# Channels.net
KiCad netlist of a schematic drawn in Altium Designer
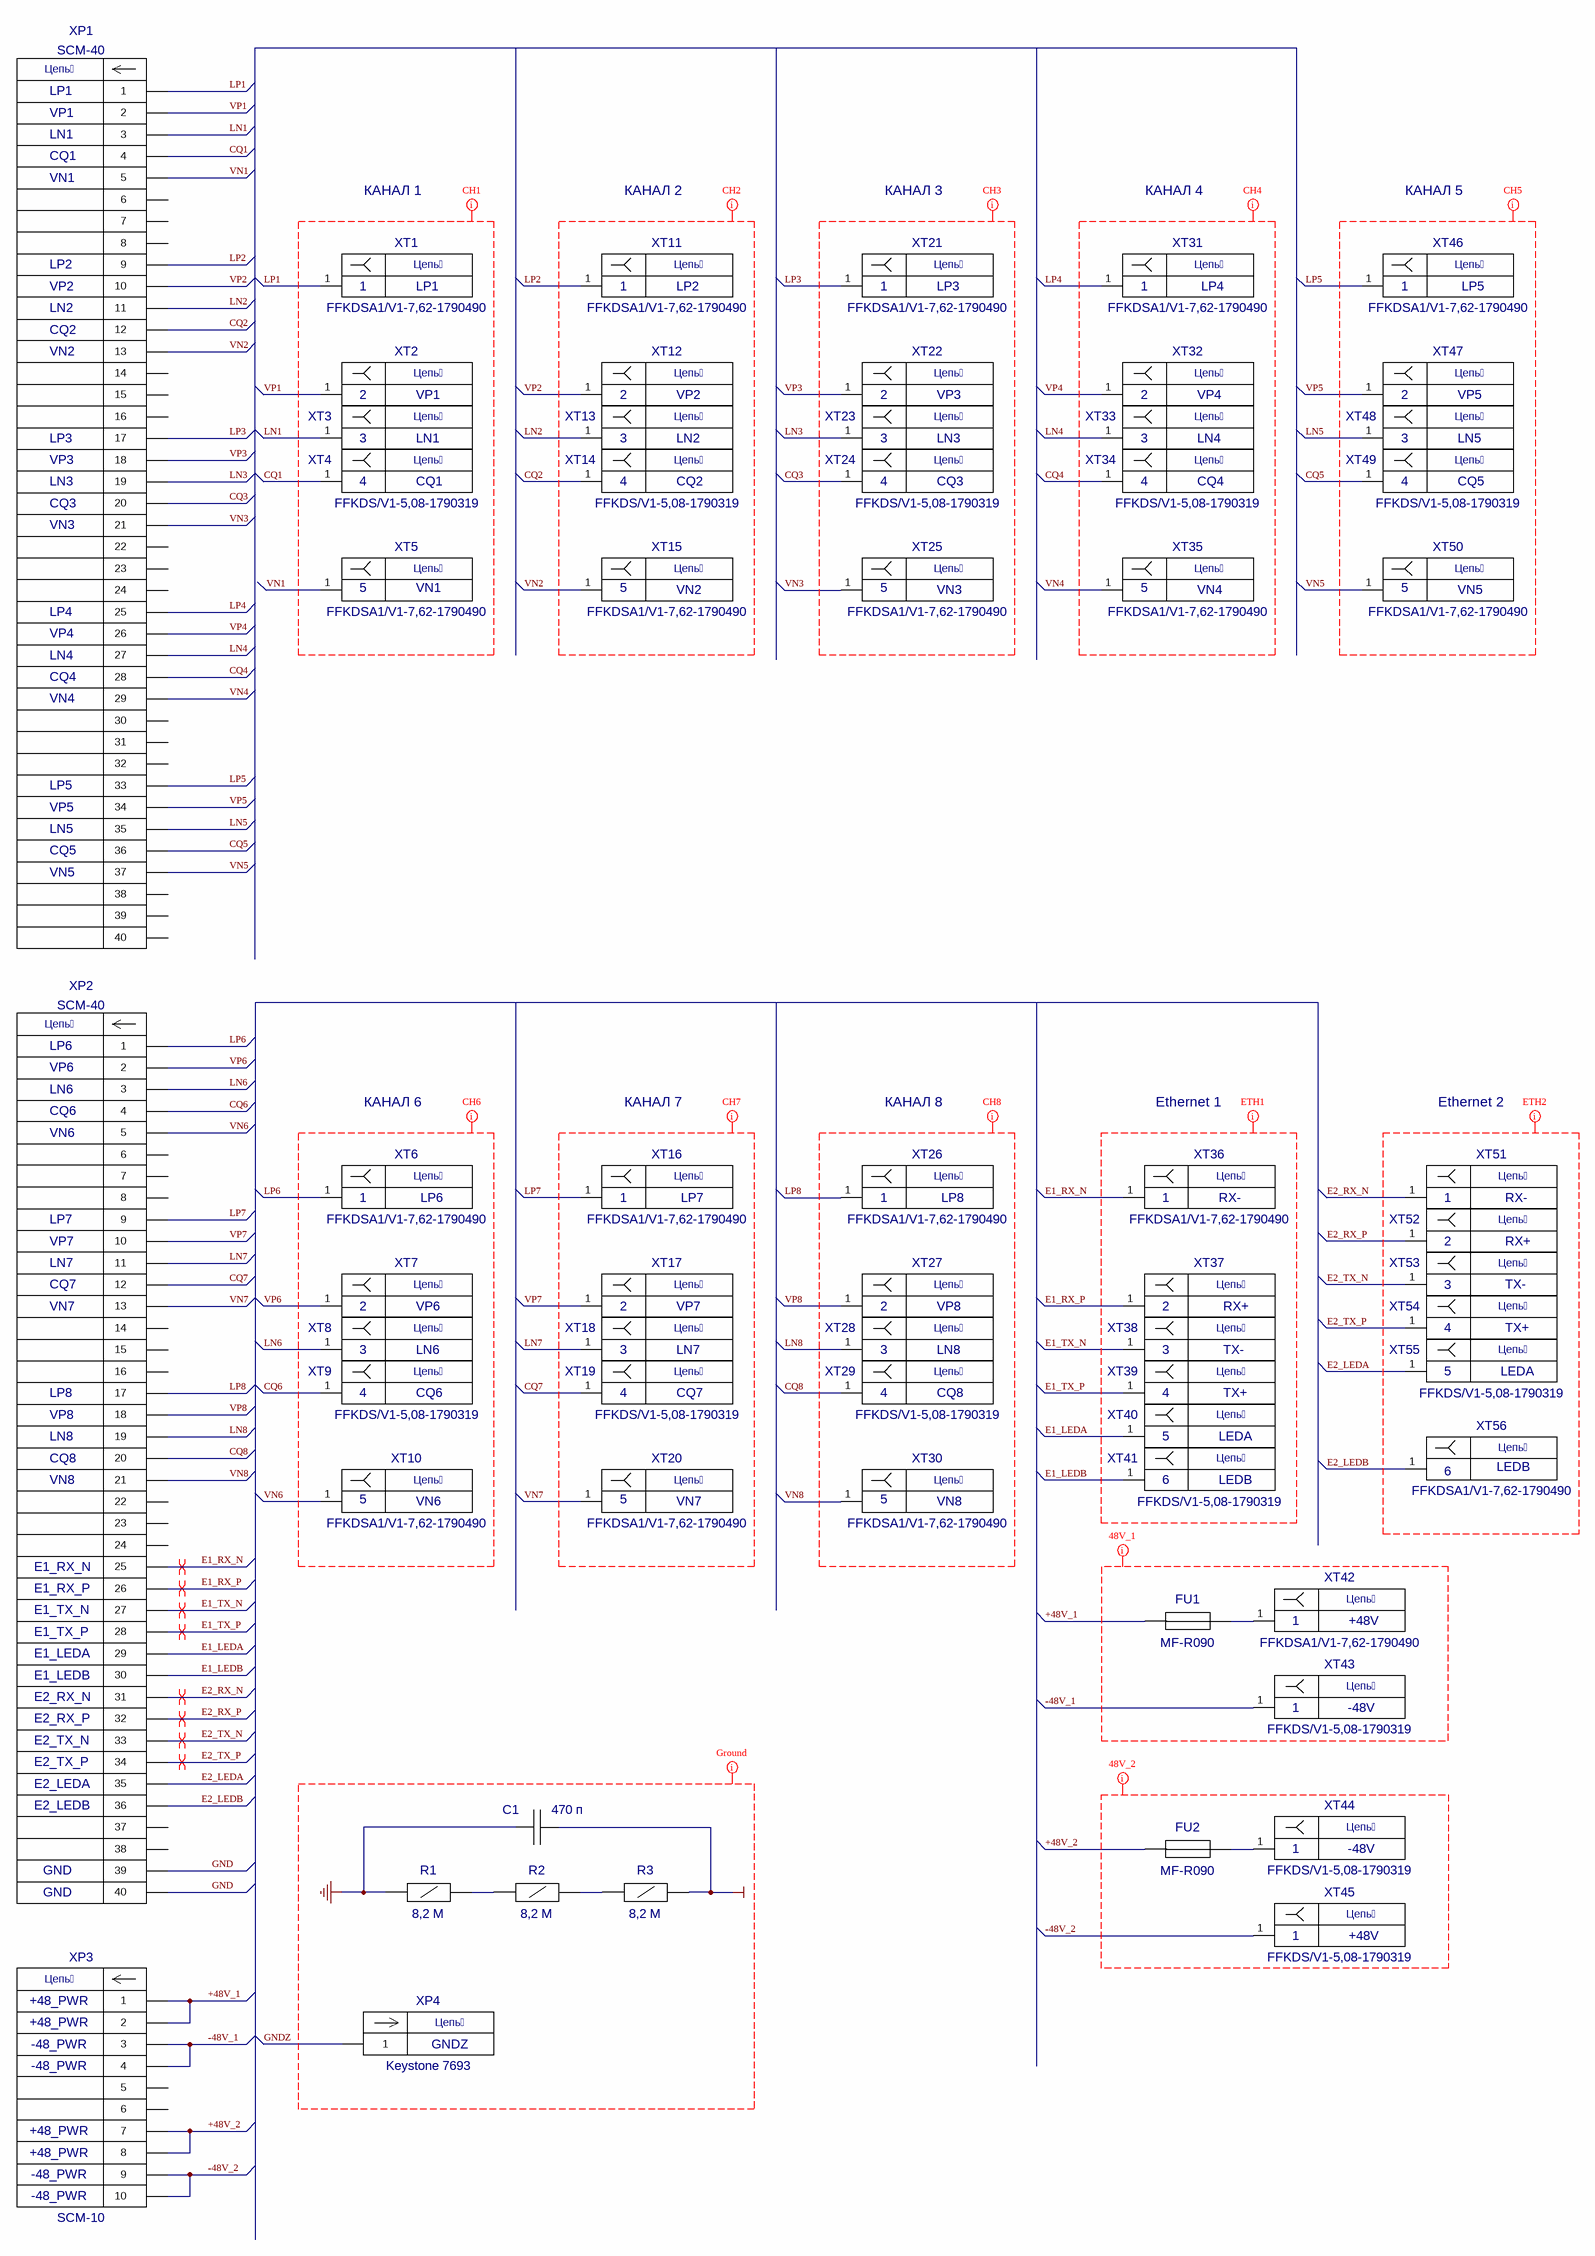
[diagram p0: Channels.SchDoc]

(export (version "E")
  (design (tool "Eeschema 10.0.6"))
  (components
    (comp (ref "C1")
      (value "470 п")
      (footprint "1812")
      (fields
        (field (name "TOLERANCE") "± 10 %")
        (field (name "VOLTAGE") "3 кВ")
        (field (name "Comment") "C1812")
      )
      (libsource (lib "Capacitor-IPC7351-N") (part "C1812"))
    )
    (comp (ref "FU1")
      (value "MF-R090")
      (footprint "MF-R090")
      (libsource (lib "Fuse-IPC7351-N") (part "MF-R090"))
    )
    (comp (ref "FU2")
      (value "MF-R090")
      (footprint "MF-R090")
      (libsource (lib "Fuse-IPC7351-N") (part "MF-R090"))
    )
    (comp (ref "R1")
      (value "8,2 М")
      (footprint "1206")
      (fields
        (field (name "POWER") "0,25 Вт")
        (field (name "TOLERANCE") "± 5 %")
        (field (name "Comment") "R1206")
      )
      (libsource (lib "Resistor-IPC7351-N") (part "R1206"))
    )
    (comp (ref "R2")
      (value "8,2 М")
      (footprint "1206")
      (fields
        (field (name "POWER") "0,25 Вт")
        (field (name "TOLERANCE") "± 5 %")
        (field (name "Comment") "R1206")
      )
      (libsource (lib "Resistor-IPC7351-N") (part "R1206"))
    )
    (comp (ref "R3")
      (value "8,2 М")
      (footprint "1206")
      (fields
        (field (name "POWER") "0,25 Вт")
        (field (name "TOLERANCE") "± 5 %")
        (field (name "Comment") "R1206")
      )
      (libsource (lib "Resistor-IPC7351-N") (part "R1206"))
    )
    (comp (ref "XP1")
      (value "SCM-40")
      (footprint "SCM-40")
      (libsource (lib "Connect-IPC7351-N") (part "SCM-40"))
    )
    (comp (ref "XP2")
      (value "SCM-40")
      (footprint "SCM-40")
      (libsource (lib "Connect-IPC7351-N") (part "SCM-40"))
    )
    (comp (ref "XP3")
      (value "SCM-10")
      (footprint "SCM-10")
      (libsource (lib "Connect-IPC7351-N") (part "SCM-10"))
    )
    (comp (ref "XP4")
      (value "Keystone 7693")
      (footprint "KEYSTONE 7693")
      (libsource (lib "Connect-IPC7351-N") (part "KEYSTONE 7693"))
    )
    (comp (ref "XT1")
      (value "FFKDSA1/V1-7,62-1790490")
      (footprint "FFKDSA1/V1-7,62-1790490")
      (libsource (lib "Connect-IPC7351-N") (part "FFKDSA1/V1-7,62-1790490"))
    )
    (comp (ref "XT2")
      (value "FFKDS/V1-5,08-1790319")
      (footprint "FFKDS/V1-5,08-1790319")
      (libsource (lib "Connect-IPC7351-N") (part "FFKDS/V1-5,08-1790319"))
    )
    (comp (ref "XT3")
      (value "FFKDS/V1-5,08-1790319")
      (footprint "FFKDS/V1-5,08-1790319")
      (libsource (lib "Connect-IPC7351-N") (part "FFKDS/V1-5,08-1790319"))
    )
    (comp (ref "XT4")
      (value "FFKDS/V1-5,08-1790319")
      (footprint "FFKDS/V1-5,08-1790319")
      (libsource (lib "Connect-IPC7351-N") (part "FFKDS/V1-5,08-1790319"))
    )
    (comp (ref "XT5")
      (value "FFKDSA1/V1-7,62-1790490")
      (footprint "FFKDSA1/V1-7,62-1790490")
      (libsource (lib "Connect-IPC7351-N") (part "FFKDSA1/V1-7,62-1790490"))
    )
    (comp (ref "XT6")
      (value "FFKDSA1/V1-7,62-1790490")
      (footprint "FFKDSA1/V1-7,62-1790490")
      (libsource (lib "Connect-IPC7351-N") (part "FFKDSA1/V1-7,62-1790490"))
    )
    (comp (ref "XT7")
      (value "FFKDS/V1-5,08-1790319")
      (footprint "FFKDS/V1-5,08-1790319")
      (libsource (lib "Connect-IPC7351-N") (part "FFKDS/V1-5,08-1790319"))
    )
    (comp (ref "XT8")
      (value "FFKDS/V1-5,08-1790319")
      (footprint "FFKDS/V1-5,08-1790319")
      (libsource (lib "Connect-IPC7351-N") (part "FFKDS/V1-5,08-1790319"))
    )
    (comp (ref "XT9")
      (value "FFKDS/V1-5,08-1790319")
      (footprint "FFKDS/V1-5,08-1790319")
      (libsource (lib "Connect-IPC7351-N") (part "FFKDS/V1-5,08-1790319"))
    )
    (comp (ref "XT10")
      (value "FFKDSA1/V1-7,62-1790490")
      (footprint "FFKDSA1/V1-7,62-1790490")
      (libsource (lib "Connect-IPC7351-N") (part "FFKDSA1/V1-7,62-1790490"))
    )
    (comp (ref "XT11")
      (value "FFKDSA1/V1-7,62-1790490")
      (footprint "FFKDSA1/V1-7,62-1790490")
      (libsource (lib "Connect-IPC7351-N") (part "FFKDSA1/V1-7,62-1790490"))
    )
    (comp (ref "XT12")
      (value "FFKDS/V1-5,08-1790319")
      (footprint "FFKDS/V1-5,08-1790319")
      (libsource (lib "Connect-IPC7351-N") (part "FFKDS/V1-5,08-1790319"))
    )
    (comp (ref "XT13")
      (value "FFKDS/V1-5,08-1790319")
      (footprint "FFKDS/V1-5,08-1790319")
      (libsource (lib "Connect-IPC7351-N") (part "FFKDS/V1-5,08-1790319"))
    )
    (comp (ref "XT14")
      (value "FFKDS/V1-5,08-1790319")
      (footprint "FFKDS/V1-5,08-1790319")
      (libsource (lib "Connect-IPC7351-N") (part "FFKDS/V1-5,08-1790319"))
    )
    (comp (ref "XT15")
      (value "FFKDSA1/V1-7,62-1790490")
      (footprint "FFKDSA1/V1-7,62-1790490")
      (libsource (lib "Connect-IPC7351-N") (part "FFKDSA1/V1-7,62-1790490"))
    )
    (comp (ref "XT16")
      (value "FFKDSA1/V1-7,62-1790490")
      (footprint "FFKDSA1/V1-7,62-1790490")
      (libsource (lib "Connect-IPC7351-N") (part "FFKDSA1/V1-7,62-1790490"))
    )
    (comp (ref "XT17")
      (value "FFKDS/V1-5,08-1790319")
      (footprint "FFKDS/V1-5,08-1790319")
      (libsource (lib "Connect-IPC7351-N") (part "FFKDS/V1-5,08-1790319"))
    )
    (comp (ref "XT18")
      (value "FFKDS/V1-5,08-1790319")
      (footprint "FFKDS/V1-5,08-1790319")
      (libsource (lib "Connect-IPC7351-N") (part "FFKDS/V1-5,08-1790319"))
    )
    (comp (ref "XT19")
      (value "FFKDS/V1-5,08-1790319")
      (footprint "FFKDS/V1-5,08-1790319")
      (libsource (lib "Connect-IPC7351-N") (part "FFKDS/V1-5,08-1790319"))
    )
    (comp (ref "XT20")
      (value "FFKDSA1/V1-7,62-1790490")
      (footprint "FFKDSA1/V1-7,62-1790490")
      (libsource (lib "Connect-IPC7351-N") (part "FFKDSA1/V1-7,62-1790490"))
    )
    (comp (ref "XT21")
      (value "FFKDSA1/V1-7,62-1790490")
      (footprint "FFKDSA1/V1-7,62-1790490")
      (libsource (lib "Connect-IPC7351-N") (part "FFKDSA1/V1-7,62-1790490"))
    )
    (comp (ref "XT22")
      (value "FFKDS/V1-5,08-1790319")
      (footprint "FFKDS/V1-5,08-1790319")
      (libsource (lib "Connect-IPC7351-N") (part "FFKDS/V1-5,08-1790319"))
    )
    (comp (ref "XT23")
      (value "FFKDS/V1-5,08-1790319")
      (footprint "FFKDS/V1-5,08-1790319")
      (libsource (lib "Connect-IPC7351-N") (part "FFKDS/V1-5,08-1790319"))
    )
    (comp (ref "XT24")
      (value "FFKDS/V1-5,08-1790319")
      (footprint "FFKDS/V1-5,08-1790319")
      (libsource (lib "Connect-IPC7351-N") (part "FFKDS/V1-5,08-1790319"))
    )
    (comp (ref "XT25")
      (value "FFKDSA1/V1-7,62-1790490")
      (footprint "FFKDSA1/V1-7,62-1790490")
      (libsource (lib "Connect-IPC7351-N") (part "FFKDSA1/V1-7,62-1790490"))
    )
    (comp (ref "XT26")
      (value "FFKDSA1/V1-7,62-1790490")
      (footprint "FFKDSA1/V1-7,62-1790490")
      (libsource (lib "Connect-IPC7351-N") (part "FFKDSA1/V1-7,62-1790490"))
    )
    (comp (ref "XT27")
      (value "FFKDS/V1-5,08-1790319")
      (footprint "FFKDS/V1-5,08-1790319")
      (libsource (lib "Connect-IPC7351-N") (part "FFKDS/V1-5,08-1790319"))
    )
    (comp (ref "XT28")
      (value "FFKDS/V1-5,08-1790319")
      (footprint "FFKDS/V1-5,08-1790319")
      (libsource (lib "Connect-IPC7351-N") (part "FFKDS/V1-5,08-1790319"))
    )
    (comp (ref "XT29")
      (value "FFKDS/V1-5,08-1790319")
      (footprint "FFKDS/V1-5,08-1790319")
      (libsource (lib "Connect-IPC7351-N") (part "FFKDS/V1-5,08-1790319"))
    )
    (comp (ref "XT30")
      (value "FFKDSA1/V1-7,62-1790490")
      (footprint "FFKDSA1/V1-7,62-1790490")
      (libsource (lib "Connect-IPC7351-N") (part "FFKDSA1/V1-7,62-1790490"))
    )
    (comp (ref "XT31")
      (value "FFKDSA1/V1-7,62-1790490")
      (footprint "FFKDSA1/V1-7,62-1790490")
      (libsource (lib "Connect-IPC7351-N") (part "FFKDSA1/V1-7,62-1790490"))
    )
    (comp (ref "XT32")
      (value "FFKDS/V1-5,08-1790319")
      (footprint "FFKDS/V1-5,08-1790319")
      (libsource (lib "Connect-IPC7351-N") (part "FFKDS/V1-5,08-1790319"))
    )
    (comp (ref "XT33")
      (value "FFKDS/V1-5,08-1790319")
      (footprint "FFKDS/V1-5,08-1790319")
      (libsource (lib "Connect-IPC7351-N") (part "FFKDS/V1-5,08-1790319"))
    )
    (comp (ref "XT34")
      (value "FFKDS/V1-5,08-1790319")
      (footprint "FFKDS/V1-5,08-1790319")
      (libsource (lib "Connect-IPC7351-N") (part "FFKDS/V1-5,08-1790319"))
    )
    (comp (ref "XT35")
      (value "FFKDSA1/V1-7,62-1790490")
      (footprint "FFKDSA1/V1-7,62-1790490")
      (libsource (lib "Connect-IPC7351-N") (part "FFKDSA1/V1-7,62-1790490"))
    )
    (comp (ref "XT36")
      (value "FFKDSA1/V1-7,62-1790490")
      (footprint "FFKDSA1/V1-7,62-1790490")
      (libsource (lib "Connect-IPC7351-N") (part "FFKDSA1/V1-7,62-1790490"))
    )
    (comp (ref "XT37")
      (value "FFKDS/V1-5,08-1790319")
      (footprint "FFKDS/V1-5,08-1790319")
      (libsource (lib "Connect-IPC7351-N") (part "FFKDS/V1-5,08-1790319"))
    )
    (comp (ref "XT38")
      (value "FFKDS/V1-5,08-1790319")
      (footprint "FFKDS/V1-5,08-1790319")
      (libsource (lib "Connect-IPC7351-N") (part "FFKDS/V1-5,08-1790319"))
    )
    (comp (ref "XT39")
      (value "FFKDS/V1-5,08-1790319")
      (footprint "FFKDS/V1-5,08-1790319")
      (libsource (lib "Connect-IPC7351-N") (part "FFKDS/V1-5,08-1790319"))
    )
    (comp (ref "XT40")
      (value "FFKDS/V1-5,08-1790319")
      (footprint "FFKDS/V1-5,08-1790319")
      (libsource (lib "Connect-IPC7351-N") (part "FFKDS/V1-5,08-1790319"))
    )
    (comp (ref "XT41")
      (value "FFKDS/V1-5,08-1790319")
      (footprint "FFKDS/V1-5,08-1790319")
      (libsource (lib "Connect-IPC7351-N") (part "FFKDS/V1-5,08-1790319"))
    )
    (comp (ref "XT42")
      (value "FFKDSA1/V1-7,62-1790490")
      (footprint "FFKDSA1/V1-7,62-1790490")
      (libsource (lib "Connect-IPC7351-N") (part "FFKDSA1/V1-7,62-1790490"))
    )
    (comp (ref "XT43")
      (value "FFKDS/V1-5,08-1790319")
      (footprint "FFKDS/V1-5,08-1790319")
      (libsource (lib "Connect-IPC7351-N") (part "FFKDS/V1-5,08-1790319"))
    )
    (comp (ref "XT44")
      (value "FFKDS/V1-5,08-1790319")
      (footprint "FFKDS/V1-5,08-1790319")
      (libsource (lib "Connect-IPC7351-N") (part "FFKDS/V1-5,08-1790319"))
    )
    (comp (ref "XT45")
      (value "FFKDS/V1-5,08-1790319")
      (footprint "FFKDS/V1-5,08-1790319")
      (libsource (lib "Connect-IPC7351-N") (part "FFKDS/V1-5,08-1790319"))
    )
    (comp (ref "XT46")
      (value "FFKDSA1/V1-7,62-1790490")
      (footprint "FFKDSA1/V1-7,62-1790490")
      (libsource (lib "Connect-IPC7351-N") (part "FFKDSA1/V1-7,62-1790490"))
    )
    (comp (ref "XT47")
      (value "FFKDS/V1-5,08-1790319")
      (footprint "FFKDS/V1-5,08-1790319")
      (libsource (lib "Connect-IPC7351-N") (part "FFKDS/V1-5,08-1790319"))
    )
    (comp (ref "XT48")
      (value "FFKDS/V1-5,08-1790319")
      (footprint "FFKDS/V1-5,08-1790319")
      (libsource (lib "Connect-IPC7351-N") (part "FFKDS/V1-5,08-1790319"))
    )
    (comp (ref "XT49")
      (value "FFKDS/V1-5,08-1790319")
      (footprint "FFKDS/V1-5,08-1790319")
      (libsource (lib "Connect-IPC7351-N") (part "FFKDS/V1-5,08-1790319"))
    )
    (comp (ref "XT50")
      (value "FFKDSA1/V1-7,62-1790490")
      (footprint "FFKDSA1/V1-7,62-1790490")
      (libsource (lib "Connect-IPC7351-N") (part "FFKDSA1/V1-7,62-1790490"))
    )
    (comp (ref "XT51")
      (value "FFKDS/V1-5,08-1790319")
      (footprint "FFKDS/V1-5,08-1790319")
      (libsource (lib "Connect-IPC7351-N") (part "FFKDS/V1-5,08-1790319"))
    )
    (comp (ref "XT52")
      (value "FFKDS/V1-5,08-1790319")
      (footprint "FFKDS/V1-5,08-1790319")
      (libsource (lib "Connect-IPC7351-N") (part "FFKDS/V1-5,08-1790319"))
    )
    (comp (ref "XT53")
      (value "FFKDS/V1-5,08-1790319")
      (footprint "FFKDS/V1-5,08-1790319")
      (libsource (lib "Connect-IPC7351-N") (part "FFKDS/V1-5,08-1790319"))
    )
    (comp (ref "XT54")
      (value "FFKDS/V1-5,08-1790319")
      (footprint "FFKDS/V1-5,08-1790319")
      (libsource (lib "Connect-IPC7351-N") (part "FFKDS/V1-5,08-1790319"))
    )
    (comp (ref "XT55")
      (value "FFKDS/V1-5,08-1790319")
      (footprint "FFKDS/V1-5,08-1790319")
      (libsource (lib "Connect-IPC7351-N") (part "FFKDS/V1-5,08-1790319"))
    )
    (comp (ref "XT56")
      (value "FFKDSA1/V1-7,62-1790490")
      (footprint "FFKDSA1/V1-7,62-1790490")
      (libsource (lib "Connect-IPC7351-N") (part "FFKDSA1/V1-7,62-1790490"))
    )
  )
  (nets
    (net (code "1") (name "/+48V_1") (class "Default")
      (node (ref "FU1") (pin "1") (pinfunction "A_1") (pintype "passive"))
      (node (ref "XP3") (pin "1") (pinfunction "1_1") (pintype "passive"))
      (node (ref "XP3") (pin "2") (pinfunction "2_2") (pintype "passive"))
    )
    (net (code "2") (name "/+48V_2") (class "Default")
      (node (ref "FU2") (pin "1") (pinfunction "A_1") (pintype "passive"))
      (node (ref "XP3") (pin "7") (pinfunction "7_7") (pintype "passive"))
      (node (ref "XP3") (pin "8") (pinfunction "8_8") (pintype "passive"))
    )
    (net (code "3") (name "/-48V_1") (class "Default")
      (node (ref "XP3") (pin "3") (pinfunction "3_3") (pintype "passive"))
      (node (ref "XP3") (pin "4") (pinfunction "4_4") (pintype "passive"))
      (node (ref "XT43") (pin "1") (pinfunction "1_1") (pintype "passive"))
    )
    (net (code "4") (name "/-48V_2") (class "Default")
      (node (ref "XP3") (pin "10") (pinfunction "10_10") (pintype "passive"))
      (node (ref "XP3") (pin "9") (pinfunction "9_9") (pintype "passive"))
      (node (ref "XT45") (pin "1") (pinfunction "1_1") (pintype "passive"))
    )
    (net (code "5") (name "/CQ1") (class "Default")
      (node (ref "XP1") (pin "4") (pinfunction "4_4") (pintype "passive"))
      (node (ref "XT4") (pin "1") (pinfunction "1_1") (pintype "passive"))
    )
    (net (code "6") (name "/CQ2") (class "Default")
      (node (ref "XP1") (pin "12") (pinfunction "12_12") (pintype "passive"))
      (node (ref "XT14") (pin "1") (pinfunction "1_1") (pintype "passive"))
    )
    (net (code "7") (name "/CQ3") (class "Default")
      (node (ref "XP1") (pin "20") (pinfunction "20_20") (pintype "passive"))
      (node (ref "XT24") (pin "1") (pinfunction "1_1") (pintype "passive"))
    )
    (net (code "8") (name "/CQ4") (class "Default")
      (node (ref "XP1") (pin "28") (pinfunction "28_28") (pintype "passive"))
      (node (ref "XT34") (pin "1") (pinfunction "1_1") (pintype "passive"))
    )
    (net (code "9") (name "/CQ5") (class "Default")
      (node (ref "XP1") (pin "36") (pinfunction "36_36") (pintype "passive"))
      (node (ref "XT49") (pin "1") (pinfunction "1_1") (pintype "passive"))
    )
    (net (code "10") (name "/CQ6") (class "Default")
      (node (ref "XP2") (pin "4") (pinfunction "4_4") (pintype "passive"))
      (node (ref "XT9") (pin "1") (pinfunction "1_1") (pintype "passive"))
    )
    (net (code "11") (name "/CQ7") (class "Default")
      (node (ref "XP2") (pin "12") (pinfunction "12_12") (pintype "passive"))
      (node (ref "XT19") (pin "1") (pinfunction "1_1") (pintype "passive"))
    )
    (net (code "12") (name "/CQ8") (class "Default")
      (node (ref "XP2") (pin "20") (pinfunction "20_20") (pintype "passive"))
      (node (ref "XT29") (pin "1") (pinfunction "1_1") (pintype "passive"))
    )
    (net (code "13") (name "/E1_LEDA") (class "Default")
      (node (ref "XP2") (pin "29") (pinfunction "29_29") (pintype "passive"))
      (node (ref "XT40") (pin "1") (pinfunction "1_1") (pintype "passive"))
    )
    (net (code "14") (name "/E1_LEDB") (class "Default")
      (node (ref "XP2") (pin "30") (pinfunction "30_30") (pintype "passive"))
      (node (ref "XT41") (pin "1") (pinfunction "1_1") (pintype "passive"))
    )
    (net (code "15") (name "/E1_RX_N") (class "Default")
      (node (ref "XP2") (pin "25") (pinfunction "25_25") (pintype "passive"))
      (node (ref "XT36") (pin "1") (pinfunction "1_1") (pintype "passive"))
    )
    (net (code "16") (name "/E1_RX_P") (class "Default")
      (node (ref "XP2") (pin "26") (pinfunction "26_26") (pintype "passive"))
      (node (ref "XT37") (pin "1") (pinfunction "1_1") (pintype "passive"))
    )
    (net (code "17") (name "/E1_TX_N") (class "Default")
      (node (ref "XP2") (pin "27") (pinfunction "27_27") (pintype "passive"))
      (node (ref "XT38") (pin "1") (pinfunction "1_1") (pintype "passive"))
    )
    (net (code "18") (name "/E1_TX_P") (class "Default")
      (node (ref "XP2") (pin "28") (pinfunction "28_28") (pintype "passive"))
      (node (ref "XT39") (pin "1") (pinfunction "1_1") (pintype "passive"))
    )
    (net (code "19") (name "/E2_LEDA") (class "Default")
      (node (ref "XP2") (pin "35") (pinfunction "35_35") (pintype "passive"))
      (node (ref "XT55") (pin "1") (pinfunction "1_1") (pintype "passive"))
    )
    (net (code "20") (name "/E2_LEDB") (class "Default")
      (node (ref "XP2") (pin "36") (pinfunction "36_36") (pintype "passive"))
      (node (ref "XT56") (pin "1") (pinfunction "1_1") (pintype "passive"))
    )
    (net (code "21") (name "/E2_RX_N") (class "Default")
      (node (ref "XP2") (pin "31") (pinfunction "31_31") (pintype "passive"))
      (node (ref "XT51") (pin "1") (pinfunction "1_1") (pintype "passive"))
    )
    (net (code "22") (name "/E2_RX_P") (class "Default")
      (node (ref "XP2") (pin "32") (pinfunction "32_32") (pintype "passive"))
      (node (ref "XT52") (pin "1") (pinfunction "1_1") (pintype "passive"))
    )
    (net (code "23") (name "/E2_TX_N") (class "Default")
      (node (ref "XP2") (pin "33") (pinfunction "33_33") (pintype "passive"))
      (node (ref "XT53") (pin "1") (pinfunction "1_1") (pintype "passive"))
    )
    (net (code "24") (name "/E2_TX_P") (class "Default")
      (node (ref "XP2") (pin "34") (pinfunction "34_34") (pintype "passive"))
      (node (ref "XT54") (pin "1") (pinfunction "1_1") (pintype "passive"))
    )
    (net (code "25") (name "/LN1") (class "Default")
      (node (ref "XP1") (pin "3") (pinfunction "3_3") (pintype "passive"))
      (node (ref "XT3") (pin "1") (pinfunction "1_1") (pintype "passive"))
    )
    (net (code "26") (name "/LN2") (class "Default")
      (node (ref "XP1") (pin "11") (pinfunction "11_11") (pintype "passive"))
      (node (ref "XT13") (pin "1") (pinfunction "1_1") (pintype "passive"))
    )
    (net (code "27") (name "/LN3") (class "Default")
      (node (ref "XP1") (pin "19") (pinfunction "19_19") (pintype "passive"))
      (node (ref "XT23") (pin "1") (pinfunction "1_1") (pintype "passive"))
    )
    (net (code "28") (name "/LN4") (class "Default")
      (node (ref "XP1") (pin "27") (pinfunction "27_27") (pintype "passive"))
      (node (ref "XT33") (pin "1") (pinfunction "1_1") (pintype "passive"))
    )
    (net (code "29") (name "/LN5") (class "Default")
      (node (ref "XP1") (pin "35") (pinfunction "35_35") (pintype "passive"))
      (node (ref "XT48") (pin "1") (pinfunction "1_1") (pintype "passive"))
    )
    (net (code "30") (name "/LN6") (class "Default")
      (node (ref "XP2") (pin "3") (pinfunction "3_3") (pintype "passive"))
      (node (ref "XT8") (pin "1") (pinfunction "1_1") (pintype "passive"))
    )
    (net (code "31") (name "/LN7") (class "Default")
      (node (ref "XP2") (pin "11") (pinfunction "11_11") (pintype "passive"))
      (node (ref "XT18") (pin "1") (pinfunction "1_1") (pintype "passive"))
    )
    (net (code "32") (name "/LN8") (class "Default")
      (node (ref "XP2") (pin "19") (pinfunction "19_19") (pintype "passive"))
      (node (ref "XT28") (pin "1") (pinfunction "1_1") (pintype "passive"))
    )
    (net (code "33") (name "/LP1") (class "Default")
      (node (ref "XP1") (pin "1") (pinfunction "1_1") (pintype "passive"))
      (node (ref "XT1") (pin "1") (pinfunction "1_1") (pintype "passive"))
    )
    (net (code "34") (name "/LP2") (class "Default")
      (node (ref "XP1") (pin "9") (pinfunction "9_9") (pintype "passive"))
      (node (ref "XT11") (pin "1") (pinfunction "1_1") (pintype "passive"))
    )
    (net (code "35") (name "/LP3") (class "Default")
      (node (ref "XP1") (pin "17") (pinfunction "17_17") (pintype "passive"))
      (node (ref "XT21") (pin "1") (pinfunction "1_1") (pintype "passive"))
    )
    (net (code "36") (name "/LP4") (class "Default")
      (node (ref "XP1") (pin "25") (pinfunction "25_25") (pintype "passive"))
      (node (ref "XT31") (pin "1") (pinfunction "1_1") (pintype "passive"))
    )
    (net (code "37") (name "/LP5") (class "Default")
      (node (ref "XP1") (pin "33") (pinfunction "33_33") (pintype "passive"))
      (node (ref "XT46") (pin "1") (pinfunction "1_1") (pintype "passive"))
    )
    (net (code "38") (name "/LP6") (class "Default")
      (node (ref "XP2") (pin "1") (pinfunction "1_1") (pintype "passive"))
      (node (ref "XT6") (pin "1") (pinfunction "1_1") (pintype "passive"))
    )
    (net (code "39") (name "/LP7") (class "Default")
      (node (ref "XP2") (pin "9") (pinfunction "9_9") (pintype "passive"))
      (node (ref "XT16") (pin "1") (pinfunction "1_1") (pintype "passive"))
    )
    (net (code "40") (name "/LP8") (class "Default")
      (node (ref "XP2") (pin "17") (pinfunction "17_17") (pintype "passive"))
      (node (ref "XT26") (pin "1") (pinfunction "1_1") (pintype "passive"))
    )
    (net (code "41") (name "/VN1") (class "Default")
      (node (ref "XP1") (pin "5") (pinfunction "5_5") (pintype "passive"))
      (node (ref "XT5") (pin "1") (pinfunction "1_1") (pintype "passive"))
    )
    (net (code "42") (name "/VN2") (class "Default")
      (node (ref "XP1") (pin "13") (pinfunction "13_13") (pintype "passive"))
      (node (ref "XT15") (pin "1") (pinfunction "1_1") (pintype "passive"))
    )
    (net (code "43") (name "/VN3") (class "Default")
      (node (ref "XP1") (pin "21") (pinfunction "21_21") (pintype "passive"))
      (node (ref "XT25") (pin "1") (pinfunction "1_1") (pintype "passive"))
    )
    (net (code "44") (name "/VN4") (class "Default")
      (node (ref "XP1") (pin "29") (pinfunction "29_29") (pintype "passive"))
      (node (ref "XT35") (pin "1") (pinfunction "1_1") (pintype "passive"))
    )
    (net (code "45") (name "/VN5") (class "Default")
      (node (ref "XP1") (pin "37") (pinfunction "37_37") (pintype "passive"))
      (node (ref "XT50") (pin "1") (pinfunction "1_1") (pintype "passive"))
    )
    (net (code "46") (name "/VN6") (class "Default")
      (node (ref "XP2") (pin "5") (pinfunction "5_5") (pintype "passive"))
      (node (ref "XT10") (pin "1") (pinfunction "1_1") (pintype "passive"))
    )
    (net (code "47") (name "/VN7") (class "Default")
      (node (ref "XP2") (pin "13") (pinfunction "13_13") (pintype "passive"))
      (node (ref "XT20") (pin "1") (pinfunction "1_1") (pintype "passive"))
    )
    (net (code "48") (name "/VN8") (class "Default")
      (node (ref "XP2") (pin "21") (pinfunction "21_21") (pintype "passive"))
      (node (ref "XT30") (pin "1") (pinfunction "1_1") (pintype "passive"))
    )
    (net (code "49") (name "/VP1") (class "Default")
      (node (ref "XP1") (pin "2") (pinfunction "2_2") (pintype "passive"))
      (node (ref "XT2") (pin "1") (pinfunction "1_1") (pintype "passive"))
    )
    (net (code "50") (name "/VP2") (class "Default")
      (node (ref "XP1") (pin "10") (pinfunction "10_10") (pintype "passive"))
      (node (ref "XT12") (pin "1") (pinfunction "1_1") (pintype "passive"))
    )
    (net (code "51") (name "/VP3") (class "Default")
      (node (ref "XP1") (pin "18") (pinfunction "18_18") (pintype "passive"))
      (node (ref "XT22") (pin "1") (pinfunction "1_1") (pintype "passive"))
    )
    (net (code "52") (name "/VP4") (class "Default")
      (node (ref "XP1") (pin "26") (pinfunction "26_26") (pintype "passive"))
      (node (ref "XT32") (pin "1") (pinfunction "1_1") (pintype "passive"))
    )
    (net (code "53") (name "/VP5") (class "Default")
      (node (ref "XP1") (pin "34") (pinfunction "34_34") (pintype "passive"))
      (node (ref "XT47") (pin "1") (pinfunction "1_1") (pintype "passive"))
    )
    (net (code "54") (name "/VP6") (class "Default")
      (node (ref "XP2") (pin "2") (pinfunction "2_2") (pintype "passive"))
      (node (ref "XT7") (pin "1") (pinfunction "1_1") (pintype "passive"))
    )
    (net (code "55") (name "/VP7") (class "Default")
      (node (ref "XP2") (pin "10") (pinfunction "10_10") (pintype "passive"))
      (node (ref "XT17") (pin "1") (pinfunction "1_1") (pintype "passive"))
    )
    (net (code "56") (name "/VP8") (class "Default")
      (node (ref "XP2") (pin "18") (pinfunction "18_18") (pintype "passive"))
      (node (ref "XT27") (pin "1") (pinfunction "1_1") (pintype "passive"))
    )
    (net (code "57") (name "GND") (class "Default")
      (node (ref "C1") (pin "2") (pinfunction "2_2") (pintype "passive"))
      (node (ref "R3") (pin "2") (pinfunction "2_2") (pintype "passive"))
      (node (ref "XP2") (pin "39") (pinfunction "39_39") (pintype "passive"))
      (node (ref "XP2") (pin "40") (pinfunction "40_40") (pintype "passive"))
    )
    (net (code "58") (name "GNDZ") (class "Default")
      (node (ref "C1") (pin "1") (pinfunction "1_1") (pintype "passive"))
      (node (ref "R1") (pin "1") (pinfunction "1_1") (pintype "passive"))
      (node (ref "XP4") (pin "1") (pinfunction "1_1") (pintype "passive"))
    )
    (net (code "59") (name "Net-(FU1-B)") (class "Default")
      (node (ref "FU1") (pin "2") (pinfunction "B_2") (pintype "passive"))
      (node (ref "XT42") (pin "1") (pinfunction "1_1") (pintype "passive"))
    )
    (net (code "60") (name "Net-(FU2-B)") (class "Default")
      (node (ref "FU2") (pin "2") (pinfunction "B_2") (pintype "passive"))
      (node (ref "XT44") (pin "1") (pinfunction "1_1") (pintype "passive"))
    )
    (net (code "61") (name "Net-(R1-Pad2)") (class "Default")
      (node (ref "R1") (pin "2") (pinfunction "2_2") (pintype "passive"))
      (node (ref "R2") (pin "1") (pinfunction "1_1") (pintype "passive"))
    )
    (net (code "62") (name "Net-(R2-Pad2)") (class "Default")
      (node (ref "R2") (pin "2") (pinfunction "2_2") (pintype "passive"))
      (node (ref "R3") (pin "1") (pinfunction "1_1") (pintype "passive"))
    )
    (net (code "63") (name "unconnected-(XP1-Pad6)") (class "Default")
      (node (ref "XP1") (pin "6") (pinfunction "6_6") (pintype "passive"))
    )
    (net (code "64") (name "unconnected-(XP1-Pad7)") (class "Default")
      (node (ref "XP1") (pin "7") (pinfunction "7_7") (pintype "passive"))
    )
    (net (code "65") (name "unconnected-(XP1-Pad8)") (class "Default")
      (node (ref "XP1") (pin "8") (pinfunction "8_8") (pintype "passive"))
    )
    (net (code "66") (name "unconnected-(XP1-Pad14)") (class "Default")
      (node (ref "XP1") (pin "14") (pinfunction "14_14") (pintype "passive"))
    )
    (net (code "67") (name "unconnected-(XP1-Pad15)") (class "Default")
      (node (ref "XP1") (pin "15") (pinfunction "15_15") (pintype "passive"))
    )
    (net (code "68") (name "unconnected-(XP1-Pad16)") (class "Default")
      (node (ref "XP1") (pin "16") (pinfunction "16_16") (pintype "passive"))
    )
    (net (code "69") (name "unconnected-(XP1-Pad22)") (class "Default")
      (node (ref "XP1") (pin "22") (pinfunction "22_22") (pintype "passive"))
    )
    (net (code "70") (name "unconnected-(XP1-Pad23)") (class "Default")
      (node (ref "XP1") (pin "23") (pinfunction "23_23") (pintype "passive"))
    )
    (net (code "71") (name "unconnected-(XP1-Pad24)") (class "Default")
      (node (ref "XP1") (pin "24") (pinfunction "24_24") (pintype "passive"))
    )
    (net (code "72") (name "unconnected-(XP1-Pad30)") (class "Default")
      (node (ref "XP1") (pin "30") (pinfunction "30_30") (pintype "passive"))
    )
    (net (code "73") (name "unconnected-(XP1-Pad31)") (class "Default")
      (node (ref "XP1") (pin "31") (pinfunction "31_31") (pintype "passive"))
    )
    (net (code "74") (name "unconnected-(XP1-Pad32)") (class "Default")
      (node (ref "XP1") (pin "32") (pinfunction "32_32") (pintype "passive"))
    )
    (net (code "75") (name "unconnected-(XP1-Pad38)") (class "Default")
      (node (ref "XP1") (pin "38") (pinfunction "38_38") (pintype "passive"))
    )
    (net (code "76") (name "unconnected-(XP1-Pad39)") (class "Default")
      (node (ref "XP1") (pin "39") (pinfunction "39_39") (pintype "passive"))
    )
    (net (code "77") (name "unconnected-(XP1-Pad40)") (class "Default")
      (node (ref "XP1") (pin "40") (pinfunction "40_40") (pintype "passive"))
    )
    (net (code "78") (name "unconnected-(XP2-Pad6)") (class "Default")
      (node (ref "XP2") (pin "6") (pinfunction "6_6") (pintype "passive"))
    )
    (net (code "79") (name "unconnected-(XP2-Pad7)") (class "Default")
      (node (ref "XP2") (pin "7") (pinfunction "7_7") (pintype "passive"))
    )
    (net (code "80") (name "unconnected-(XP2-Pad8)") (class "Default")
      (node (ref "XP2") (pin "8") (pinfunction "8_8") (pintype "passive"))
    )
    (net (code "81") (name "unconnected-(XP2-Pad14)") (class "Default")
      (node (ref "XP2") (pin "14") (pinfunction "14_14") (pintype "passive"))
    )
    (net (code "82") (name "unconnected-(XP2-Pad15)") (class "Default")
      (node (ref "XP2") (pin "15") (pinfunction "15_15") (pintype "passive"))
    )
    (net (code "83") (name "unconnected-(XP2-Pad16)") (class "Default")
      (node (ref "XP2") (pin "16") (pinfunction "16_16") (pintype "passive"))
    )
    (net (code "84") (name "unconnected-(XP2-Pad22)") (class "Default")
      (node (ref "XP2") (pin "22") (pinfunction "22_22") (pintype "passive"))
    )
    (net (code "85") (name "unconnected-(XP2-Pad23)") (class "Default")
      (node (ref "XP2") (pin "23") (pinfunction "23_23") (pintype "passive"))
    )
    (net (code "86") (name "unconnected-(XP2-Pad24)") (class "Default")
      (node (ref "XP2") (pin "24") (pinfunction "24_24") (pintype "passive"))
    )
    (net (code "87") (name "unconnected-(XP2-Pad37)") (class "Default")
      (node (ref "XP2") (pin "37") (pinfunction "37_37") (pintype "passive"))
    )
    (net (code "88") (name "unconnected-(XP2-Pad38)") (class "Default")
      (node (ref "XP2") (pin "38") (pinfunction "38_38") (pintype "passive"))
    )
    (net (code "89") (name "unconnected-(XP3-Pad5)") (class "Default")
      (node (ref "XP3") (pin "5") (pinfunction "5_5") (pintype "passive"))
    )
    (net (code "90") (name "unconnected-(XP3-Pad6)") (class "Default")
      (node (ref "XP3") (pin "6") (pinfunction "6_6") (pintype "passive"))
    )
    (net (code "91") (name "unconnected-(XP4-Pad2)") (class "Default")
      (node (ref "XP4") (pin "2") (pintype "passive"))
    )
    (net (code "92") (name "unconnected-(XP4-Pad3)") (class "Default")
      (node (ref "XP4") (pin "3") (pintype "passive"))
    )
    (net (code "93") (name "unconnected-(XP4-Pad4)") (class "Default")
      (node (ref "XP4") (pin "4") (pintype "passive"))
    )
    (net (code "94") (name "unconnected-(XT1-Pad2)") (class "Default")
      (node (ref "XT1") (pin "2") (pintype "passive"))
    )
    (net (code "95") (name "unconnected-(XT1-Pad2)_1") (class "Default")
      (node (ref "XT1") (pin "2") (pintype "passive"))
    )
    (net (code "96") (name "unconnected-(XT2-Pad2)") (class "Default")
      (node (ref "XT2") (pin "2") (pintype "passive"))
    )
    (net (code "97") (name "unconnected-(XT2-Pad2)_1") (class "Default")
      (node (ref "XT2") (pin "2") (pintype "passive"))
    )
    (net (code "98") (name "unconnected-(XT3-Pad2)") (class "Default")
      (node (ref "XT3") (pin "2") (pintype "passive"))
    )
    (net (code "99") (name "unconnected-(XT3-Pad2)_1") (class "Default")
      (node (ref "XT3") (pin "2") (pintype "passive"))
    )
    (net (code "100") (name "unconnected-(XT4-Pad2)") (class "Default")
      (node (ref "XT4") (pin "2") (pintype "passive"))
    )
    (net (code "101") (name "unconnected-(XT4-Pad2)_1") (class "Default")
      (node (ref "XT4") (pin "2") (pintype "passive"))
    )
    (net (code "102") (name "unconnected-(XT5-Pad2)") (class "Default")
      (node (ref "XT5") (pin "2") (pintype "passive"))
    )
    (net (code "103") (name "unconnected-(XT5-Pad2)_1") (class "Default")
      (node (ref "XT5") (pin "2") (pintype "passive"))
    )
    (net (code "104") (name "unconnected-(XT6-Pad2)") (class "Default")
      (node (ref "XT6") (pin "2") (pintype "passive"))
    )
    (net (code "105") (name "unconnected-(XT6-Pad2)_1") (class "Default")
      (node (ref "XT6") (pin "2") (pintype "passive"))
    )
    (net (code "106") (name "unconnected-(XT7-Pad2)") (class "Default")
      (node (ref "XT7") (pin "2") (pintype "passive"))
    )
    (net (code "107") (name "unconnected-(XT7-Pad2)_1") (class "Default")
      (node (ref "XT7") (pin "2") (pintype "passive"))
    )
    (net (code "108") (name "unconnected-(XT8-Pad2)") (class "Default")
      (node (ref "XT8") (pin "2") (pintype "passive"))
    )
    (net (code "109") (name "unconnected-(XT8-Pad2)_1") (class "Default")
      (node (ref "XT8") (pin "2") (pintype "passive"))
    )
    (net (code "110") (name "unconnected-(XT9-Pad2)") (class "Default")
      (node (ref "XT9") (pin "2") (pintype "passive"))
    )
    (net (code "111") (name "unconnected-(XT9-Pad2)_1") (class "Default")
      (node (ref "XT9") (pin "2") (pintype "passive"))
    )
    (net (code "112") (name "unconnected-(XT10-Pad2)") (class "Default")
      (node (ref "XT10") (pin "2") (pintype "passive"))
    )
    (net (code "113") (name "unconnected-(XT10-Pad2)_1") (class "Default")
      (node (ref "XT10") (pin "2") (pintype "passive"))
    )
    (net (code "114") (name "unconnected-(XT11-Pad2)") (class "Default")
      (node (ref "XT11") (pin "2") (pintype "passive"))
    )
    (net (code "115") (name "unconnected-(XT11-Pad2)_1") (class "Default")
      (node (ref "XT11") (pin "2") (pintype "passive"))
    )
    (net (code "116") (name "unconnected-(XT12-Pad2)") (class "Default")
      (node (ref "XT12") (pin "2") (pintype "passive"))
    )
    (net (code "117") (name "unconnected-(XT12-Pad2)_1") (class "Default")
      (node (ref "XT12") (pin "2") (pintype "passive"))
    )
    (net (code "118") (name "unconnected-(XT13-Pad2)") (class "Default")
      (node (ref "XT13") (pin "2") (pintype "passive"))
    )
    (net (code "119") (name "unconnected-(XT13-Pad2)_1") (class "Default")
      (node (ref "XT13") (pin "2") (pintype "passive"))
    )
    (net (code "120") (name "unconnected-(XT14-Pad2)") (class "Default")
      (node (ref "XT14") (pin "2") (pintype "passive"))
    )
    (net (code "121") (name "unconnected-(XT14-Pad2)_1") (class "Default")
      (node (ref "XT14") (pin "2") (pintype "passive"))
    )
    (net (code "122") (name "unconnected-(XT15-Pad2)") (class "Default")
      (node (ref "XT15") (pin "2") (pintype "passive"))
    )
    (net (code "123") (name "unconnected-(XT15-Pad2)_1") (class "Default")
      (node (ref "XT15") (pin "2") (pintype "passive"))
    )
    (net (code "124") (name "unconnected-(XT16-Pad2)") (class "Default")
      (node (ref "XT16") (pin "2") (pintype "passive"))
    )
    (net (code "125") (name "unconnected-(XT16-Pad2)_1") (class "Default")
      (node (ref "XT16") (pin "2") (pintype "passive"))
    )
    (net (code "126") (name "unconnected-(XT17-Pad2)") (class "Default")
      (node (ref "XT17") (pin "2") (pintype "passive"))
    )
    (net (code "127") (name "unconnected-(XT17-Pad2)_1") (class "Default")
      (node (ref "XT17") (pin "2") (pintype "passive"))
    )
    (net (code "128") (name "unconnected-(XT18-Pad2)") (class "Default")
      (node (ref "XT18") (pin "2") (pintype "passive"))
    )
    (net (code "129") (name "unconnected-(XT18-Pad2)_1") (class "Default")
      (node (ref "XT18") (pin "2") (pintype "passive"))
    )
    (net (code "130") (name "unconnected-(XT19-Pad2)") (class "Default")
      (node (ref "XT19") (pin "2") (pintype "passive"))
    )
    (net (code "131") (name "unconnected-(XT19-Pad2)_1") (class "Default")
      (node (ref "XT19") (pin "2") (pintype "passive"))
    )
    (net (code "132") (name "unconnected-(XT20-Pad2)") (class "Default")
      (node (ref "XT20") (pin "2") (pintype "passive"))
    )
    (net (code "133") (name "unconnected-(XT20-Pad2)_1") (class "Default")
      (node (ref "XT20") (pin "2") (pintype "passive"))
    )
    (net (code "134") (name "unconnected-(XT21-Pad2)") (class "Default")
      (node (ref "XT21") (pin "2") (pintype "passive"))
    )
    (net (code "135") (name "unconnected-(XT21-Pad2)_1") (class "Default")
      (node (ref "XT21") (pin "2") (pintype "passive"))
    )
    (net (code "136") (name "unconnected-(XT22-Pad2)") (class "Default")
      (node (ref "XT22") (pin "2") (pintype "passive"))
    )
    (net (code "137") (name "unconnected-(XT22-Pad2)_1") (class "Default")
      (node (ref "XT22") (pin "2") (pintype "passive"))
    )
    (net (code "138") (name "unconnected-(XT23-Pad2)") (class "Default")
      (node (ref "XT23") (pin "2") (pintype "passive"))
    )
    (net (code "139") (name "unconnected-(XT23-Pad2)_1") (class "Default")
      (node (ref "XT23") (pin "2") (pintype "passive"))
    )
    (net (code "140") (name "unconnected-(XT24-Pad2)") (class "Default")
      (node (ref "XT24") (pin "2") (pintype "passive"))
    )
    (net (code "141") (name "unconnected-(XT24-Pad2)_1") (class "Default")
      (node (ref "XT24") (pin "2") (pintype "passive"))
    )
    (net (code "142") (name "unconnected-(XT25-Pad2)") (class "Default")
      (node (ref "XT25") (pin "2") (pintype "passive"))
    )
    (net (code "143") (name "unconnected-(XT25-Pad2)_1") (class "Default")
      (node (ref "XT25") (pin "2") (pintype "passive"))
    )
    (net (code "144") (name "unconnected-(XT26-Pad2)") (class "Default")
      (node (ref "XT26") (pin "2") (pintype "passive"))
    )
    (net (code "145") (name "unconnected-(XT26-Pad2)_1") (class "Default")
      (node (ref "XT26") (pin "2") (pintype "passive"))
    )
    (net (code "146") (name "unconnected-(XT27-Pad2)") (class "Default")
      (node (ref "XT27") (pin "2") (pintype "passive"))
    )
    (net (code "147") (name "unconnected-(XT27-Pad2)_1") (class "Default")
      (node (ref "XT27") (pin "2") (pintype "passive"))
    )
    (net (code "148") (name "unconnected-(XT28-Pad2)") (class "Default")
      (node (ref "XT28") (pin "2") (pintype "passive"))
    )
    (net (code "149") (name "unconnected-(XT28-Pad2)_1") (class "Default")
      (node (ref "XT28") (pin "2") (pintype "passive"))
    )
    (net (code "150") (name "unconnected-(XT29-Pad2)") (class "Default")
      (node (ref "XT29") (pin "2") (pintype "passive"))
    )
    (net (code "151") (name "unconnected-(XT29-Pad2)_1") (class "Default")
      (node (ref "XT29") (pin "2") (pintype "passive"))
    )
    (net (code "152") (name "unconnected-(XT30-Pad2)") (class "Default")
      (node (ref "XT30") (pin "2") (pintype "passive"))
    )
    (net (code "153") (name "unconnected-(XT30-Pad2)_1") (class "Default")
      (node (ref "XT30") (pin "2") (pintype "passive"))
    )
    (net (code "154") (name "unconnected-(XT31-Pad2)") (class "Default")
      (node (ref "XT31") (pin "2") (pintype "passive"))
    )
    (net (code "155") (name "unconnected-(XT31-Pad2)_1") (class "Default")
      (node (ref "XT31") (pin "2") (pintype "passive"))
    )
    (net (code "156") (name "unconnected-(XT32-Pad2)") (class "Default")
      (node (ref "XT32") (pin "2") (pintype "passive"))
    )
    (net (code "157") (name "unconnected-(XT32-Pad2)_1") (class "Default")
      (node (ref "XT32") (pin "2") (pintype "passive"))
    )
    (net (code "158") (name "unconnected-(XT33-Pad2)") (class "Default")
      (node (ref "XT33") (pin "2") (pintype "passive"))
    )
    (net (code "159") (name "unconnected-(XT33-Pad2)_1") (class "Default")
      (node (ref "XT33") (pin "2") (pintype "passive"))
    )
    (net (code "160") (name "unconnected-(XT34-Pad2)") (class "Default")
      (node (ref "XT34") (pin "2") (pintype "passive"))
    )
    (net (code "161") (name "unconnected-(XT34-Pad2)_1") (class "Default")
      (node (ref "XT34") (pin "2") (pintype "passive"))
    )
    (net (code "162") (name "unconnected-(XT35-Pad2)") (class "Default")
      (node (ref "XT35") (pin "2") (pintype "passive"))
    )
    (net (code "163") (name "unconnected-(XT35-Pad2)_1") (class "Default")
      (node (ref "XT35") (pin "2") (pintype "passive"))
    )
    (net (code "164") (name "unconnected-(XT36-Pad2)") (class "Default")
      (node (ref "XT36") (pin "2") (pintype "passive"))
    )
    (net (code "165") (name "unconnected-(XT36-Pad2)_1") (class "Default")
      (node (ref "XT36") (pin "2") (pintype "passive"))
    )
    (net (code "166") (name "unconnected-(XT37-Pad2)") (class "Default")
      (node (ref "XT37") (pin "2") (pintype "passive"))
    )
    (net (code "167") (name "unconnected-(XT37-Pad2)_1") (class "Default")
      (node (ref "XT37") (pin "2") (pintype "passive"))
    )
    (net (code "168") (name "unconnected-(XT38-Pad2)") (class "Default")
      (node (ref "XT38") (pin "2") (pintype "passive"))
    )
    (net (code "169") (name "unconnected-(XT38-Pad2)_1") (class "Default")
      (node (ref "XT38") (pin "2") (pintype "passive"))
    )
    (net (code "170") (name "unconnected-(XT39-Pad2)") (class "Default")
      (node (ref "XT39") (pin "2") (pintype "passive"))
    )
    (net (code "171") (name "unconnected-(XT39-Pad2)_1") (class "Default")
      (node (ref "XT39") (pin "2") (pintype "passive"))
    )
    (net (code "172") (name "unconnected-(XT40-Pad2)") (class "Default")
      (node (ref "XT40") (pin "2") (pintype "passive"))
    )
    (net (code "173") (name "unconnected-(XT40-Pad2)_1") (class "Default")
      (node (ref "XT40") (pin "2") (pintype "passive"))
    )
    (net (code "174") (name "unconnected-(XT41-Pad2)") (class "Default")
      (node (ref "XT41") (pin "2") (pintype "passive"))
    )
    (net (code "175") (name "unconnected-(XT41-Pad2)_1") (class "Default")
      (node (ref "XT41") (pin "2") (pintype "passive"))
    )
    (net (code "176") (name "unconnected-(XT42-Pad2)") (class "Default")
      (node (ref "XT42") (pin "2") (pintype "passive"))
    )
    (net (code "177") (name "unconnected-(XT42-Pad2)_1") (class "Default")
      (node (ref "XT42") (pin "2") (pintype "passive"))
    )
    (net (code "178") (name "unconnected-(XT43-Pad2)") (class "Default")
      (node (ref "XT43") (pin "2") (pintype "passive"))
    )
    (net (code "179") (name "unconnected-(XT43-Pad2)_1") (class "Default")
      (node (ref "XT43") (pin "2") (pintype "passive"))
    )
    (net (code "180") (name "unconnected-(XT44-Pad2)") (class "Default")
      (node (ref "XT44") (pin "2") (pintype "passive"))
    )
    (net (code "181") (name "unconnected-(XT44-Pad2)_1") (class "Default")
      (node (ref "XT44") (pin "2") (pintype "passive"))
    )
    (net (code "182") (name "unconnected-(XT45-Pad2)") (class "Default")
      (node (ref "XT45") (pin "2") (pintype "passive"))
    )
    (net (code "183") (name "unconnected-(XT45-Pad2)_1") (class "Default")
      (node (ref "XT45") (pin "2") (pintype "passive"))
    )
    (net (code "184") (name "unconnected-(XT46-Pad2)") (class "Default")
      (node (ref "XT46") (pin "2") (pintype "passive"))
    )
    (net (code "185") (name "unconnected-(XT46-Pad2)_1") (class "Default")
      (node (ref "XT46") (pin "2") (pintype "passive"))
    )
    (net (code "186") (name "unconnected-(XT47-Pad2)") (class "Default")
      (node (ref "XT47") (pin "2") (pintype "passive"))
    )
    (net (code "187") (name "unconnected-(XT47-Pad2)_1") (class "Default")
      (node (ref "XT47") (pin "2") (pintype "passive"))
    )
    (net (code "188") (name "unconnected-(XT48-Pad2)") (class "Default")
      (node (ref "XT48") (pin "2") (pintype "passive"))
    )
    (net (code "189") (name "unconnected-(XT48-Pad2)_1") (class "Default")
      (node (ref "XT48") (pin "2") (pintype "passive"))
    )
    (net (code "190") (name "unconnected-(XT49-Pad2)") (class "Default")
      (node (ref "XT49") (pin "2") (pintype "passive"))
    )
    (net (code "191") (name "unconnected-(XT49-Pad2)_1") (class "Default")
      (node (ref "XT49") (pin "2") (pintype "passive"))
    )
    (net (code "192") (name "unconnected-(XT50-Pad2)") (class "Default")
      (node (ref "XT50") (pin "2") (pintype "passive"))
    )
    (net (code "193") (name "unconnected-(XT50-Pad2)_1") (class "Default")
      (node (ref "XT50") (pin "2") (pintype "passive"))
    )
    (net (code "194") (name "unconnected-(XT51-Pad2)") (class "Default")
      (node (ref "XT51") (pin "2") (pintype "passive"))
    )
    (net (code "195") (name "unconnected-(XT51-Pad2)_1") (class "Default")
      (node (ref "XT51") (pin "2") (pintype "passive"))
    )
    (net (code "196") (name "unconnected-(XT52-Pad2)") (class "Default")
      (node (ref "XT52") (pin "2") (pintype "passive"))
    )
    (net (code "197") (name "unconnected-(XT52-Pad2)_1") (class "Default")
      (node (ref "XT52") (pin "2") (pintype "passive"))
    )
    (net (code "198") (name "unconnected-(XT53-Pad2)") (class "Default")
      (node (ref "XT53") (pin "2") (pintype "passive"))
    )
    (net (code "199") (name "unconnected-(XT53-Pad2)_1") (class "Default")
      (node (ref "XT53") (pin "2") (pintype "passive"))
    )
    (net (code "200") (name "unconnected-(XT54-Pad2)") (class "Default")
      (node (ref "XT54") (pin "2") (pintype "passive"))
    )
    (net (code "201") (name "unconnected-(XT54-Pad2)_1") (class "Default")
      (node (ref "XT54") (pin "2") (pintype "passive"))
    )
    (net (code "202") (name "unconnected-(XT55-Pad2)") (class "Default")
      (node (ref "XT55") (pin "2") (pintype "passive"))
    )
    (net (code "203") (name "unconnected-(XT55-Pad2)_1") (class "Default")
      (node (ref "XT55") (pin "2") (pintype "passive"))
    )
    (net (code "204") (name "unconnected-(XT56-Pad2)") (class "Default")
      (node (ref "XT56") (pin "2") (pintype "passive"))
    )
    (net (code "205") (name "unconnected-(XT56-Pad2)_1") (class "Default")
      (node (ref "XT56") (pin "2") (pintype "passive"))
    )
  )
)
